# Sheet1.net
KiCad netlist of a schematic drawn in Altium Designer
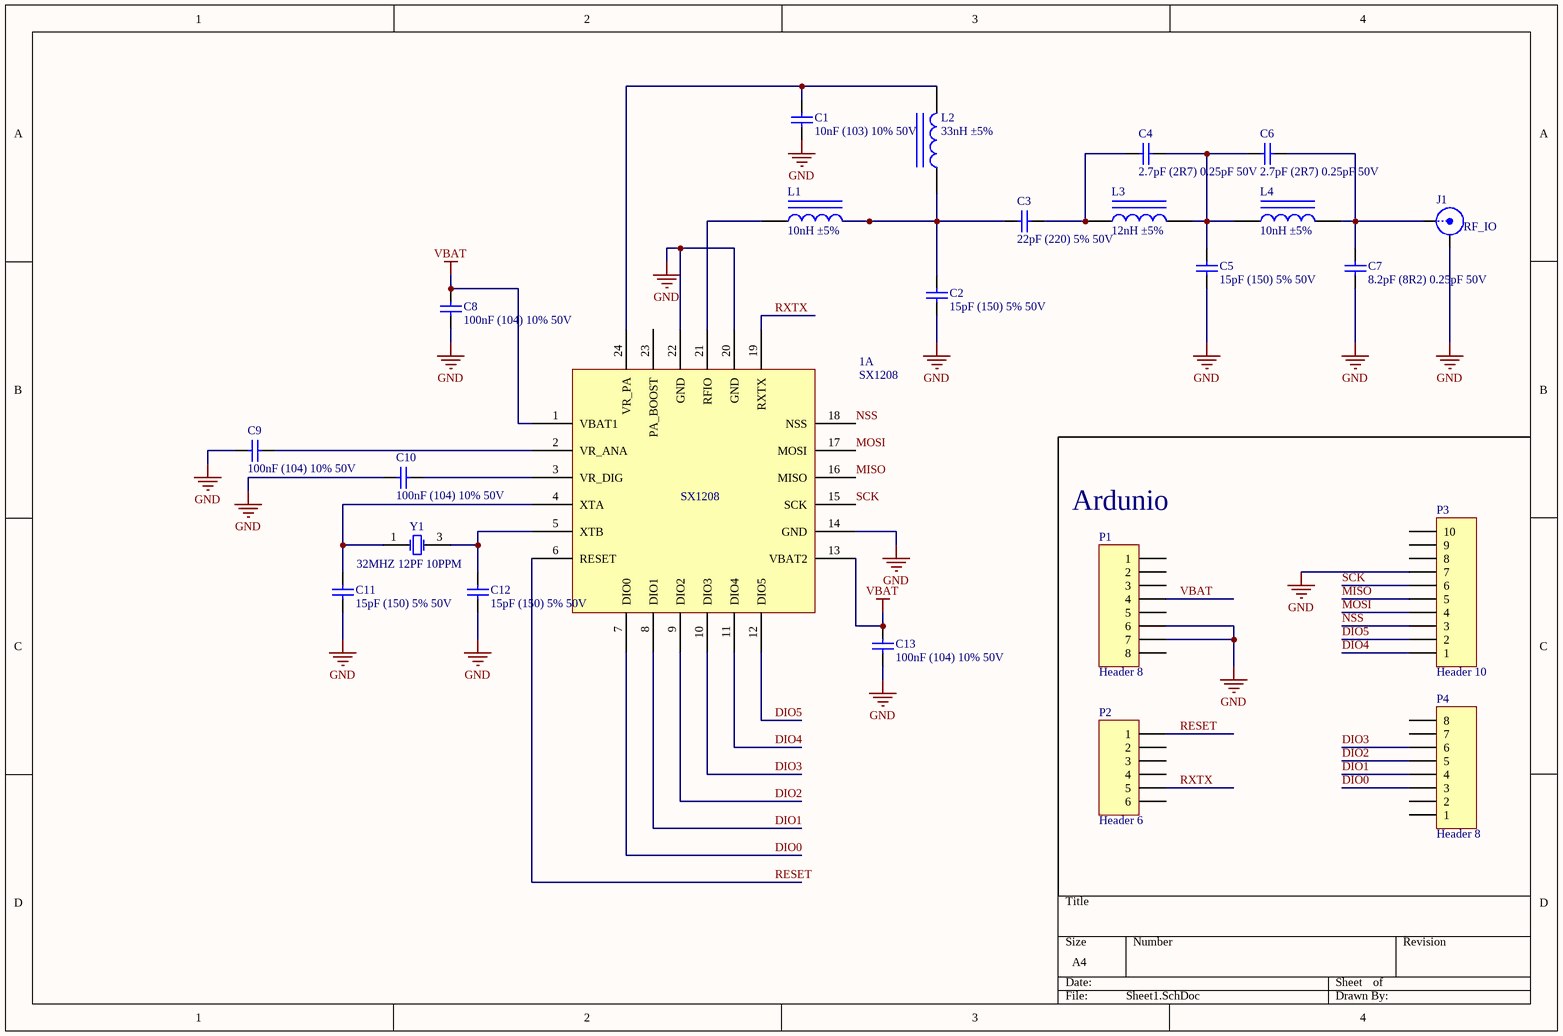
[diagram p0: Sheet1.SchDoc]

(export (version "E")
  (design (tool "Eeschema 10.0.6"))
  (components
    (comp (ref "1")
      (value "SX1208")
      (footprint "QFN-24_4x4x05P")
      (libsource (lib "SX1208") (part "Component_1"))
    )
    (comp (ref "C1")
      (value "10nF (103) 10% 50V")
      (footprint "0603_C")
      (description "贴片电容")
      (libsource (lib "Miscellaneous Devices LC") (part "0603 10nF (103) 10% 50V"))
    )
    (comp (ref "C2")
      (value "15pF (150) 5% 50V")
      (footprint "0603_C")
      (description "贴片电容")
      (libsource (lib "Miscellaneous Devices LC") (part "0603 15pF (150) 5% 50V"))
    )
    (comp (ref "C3")
      (value "22pF (220) 5% 50V")
      (footprint "0603_C")
      (description "贴片电容")
      (libsource (lib "Miscellaneous Devices LC") (part "0603 22pF (220) 5% 50V"))
    )
    (comp (ref "C4")
      (value "2.7pF (2R7) 0.25pF 50V")
      (footprint "0603_C")
      (description "贴片电容")
      (libsource (lib "Miscellaneous Devices LC") (part "0603 2.7pF (2R7) 0.25pF 50V"))
    )
    (comp (ref "C5")
      (value "15pF (150) 5% 50V")
      (footprint "0603_C")
      (description "贴片电容")
      (libsource (lib "Miscellaneous Devices LC") (part "0603 15pF (150) 5% 50V"))
    )
    (comp (ref "C6")
      (value "2.7pF (2R7) 0.25pF 50V")
      (footprint "0603_C")
      (description "贴片电容")
      (libsource (lib "Miscellaneous Devices LC") (part "0603 2.7pF (2R7) 0.25pF 50V"))
    )
    (comp (ref "C7")
      (value "8.2pF (8R2) 0.25pF 50V")
      (footprint "0603_C")
      (description "贴片电容")
      (libsource (lib "Miscellaneous Devices LC") (part "0603 8.2pF (8R2) 0.25pF 50V"))
    )
    (comp (ref "C8")
      (value "100nF (104) 10% 50V")
      (footprint "0603_C")
      (description "贴片电容")
      (libsource (lib "Miscellaneous Devices LC") (part "0603 100nF (104) 10% 50V"))
    )
    (comp (ref "C9")
      (value "100nF (104) 10% 50V")
      (footprint "0603_C")
      (description "贴片电容")
      (libsource (lib "Miscellaneous Devices LC") (part "0603 100nF (104) 10% 50V"))
    )
    (comp (ref "C10")
      (value "100nF (104) 10% 50V")
      (footprint "0603_C")
      (description "贴片电容")
      (libsource (lib "Miscellaneous Devices LC") (part "0603 100nF (104) 10% 50V"))
    )
    (comp (ref "C11")
      (value "15pF (150) 5% 50V")
      (footprint "0603_C")
      (description "贴片电容")
      (libsource (lib "Miscellaneous Devices LC") (part "0603 15pF (150) 5% 50V"))
    )
    (comp (ref "C12")
      (value "15pF (150) 5% 50V")
      (footprint "0603_C")
      (description "贴片电容")
      (libsource (lib "Miscellaneous Devices LC") (part "0603 15pF (150) 5% 50V"))
    )
    (comp (ref "C13")
      (value "100nF (104) 10% 50V")
      (footprint "0603_C")
      (description "贴片电容")
      (libsource (lib "Miscellaneous Devices LC") (part "0603 100nF (104) 10% 50V"))
    )
    (comp (ref "J1")
      (value "RF_IO")
      (footprint "PCBComponent_1")
      (description "SMB Straight Connector")
      (fields (field (name "PUBLISHER") "Altium Limited"))
      (libsource (lib "Miscellaneous Connectors") (part "SMB"))
    )
    (comp (ref "L1")
      (value "10nH ±5%")
      (footprint "0603_L")
      (description "贴片电感")
      (libsource (lib "Miscellaneous Devices LC") (part "0603 10nH 5%"))
    )
    (comp (ref "L2")
      (value "33nH ±5%")
      (footprint "0603_L")
      (description "贴片电感")
      (libsource (lib "Miscellaneous Devices LC") (part "0603 33nH 5%"))
    )
    (comp (ref "L3")
      (value "12nH ±5%")
      (footprint "0603_L")
      (description "贴片电感")
      (libsource (lib "Miscellaneous Devices LC") (part "0603 12nH 5%"))
    )
    (comp (ref "L4")
      (value "10nH ±5%")
      (footprint "0603_L")
      (description "贴片电感")
      (libsource (lib "Miscellaneous Devices LC") (part "0603 10nH 5%"))
    )
    (comp (ref "P1")
      (value "Header 8")
      (footprint "HDR1X8")
      (description "Header, 8-Pin")
      (fields (field (name "PUBLISHER") "Altium Limited"))
      (libsource (lib "Miscellaneous Connectors") (part "Header 8"))
    )
    (comp (ref "P2")
      (value "Header 6")
      (footprint "HDR1X6")
      (description "Header, 6-Pin")
      (fields (field (name "PUBLISHER") "Altium Limited"))
      (libsource (lib "Miscellaneous Connectors") (part "Header 6"))
    )
    (comp (ref "P3")
      (value "Header 10")
      (footprint "HDR1X10")
      (description "Header, 10-Pin")
      (fields (field (name "PUBLISHER") "Altium Limited"))
      (libsource (lib "Miscellaneous Connectors") (part "Header 10"))
    )
    (comp (ref "P4")
      (value "Header 8")
      (footprint "HDR1X8")
      (description "Header, 8-Pin")
      (fields (field (name "PUBLISHER") "Altium Limited"))
      (libsource (lib "") (part "Header 8_1"))
    )
    (comp (ref "Y1")
      (value "32MHZ 12PF 10PPM")
      (footprint "SMD-3225_4P")
      (description "贴片晶振")
      (libsource (lib "Miscellaneous Devices LC") (part "SMD-3225_4P  25MHZ 12PF 10PPM"))
    )
  )
  (nets
    (net (code "2") (name "/DIO0") (class "Default")
      (node (ref "1") (pin "7") (pinfunction "DIO0_7") (pintype "passive"))
      (node (ref "P4") (pin "3") (pinfunction "3_3") (pintype "passive"))
    )
    (net (code "3") (name "/DIO1") (class "Default")
      (node (ref "1") (pin "8") (pinfunction "DIO1_8") (pintype "passive"))
      (node (ref "P4") (pin "4") (pinfunction "4_4") (pintype "passive"))
    )
    (net (code "4") (name "/DIO2") (class "Default")
      (node (ref "1") (pin "9") (pinfunction "DIO2_9") (pintype "passive"))
      (node (ref "P4") (pin "5") (pinfunction "5_5") (pintype "passive"))
    )
    (net (code "5") (name "/DIO3") (class "Default")
      (node (ref "1") (pin "10") (pinfunction "DIO3_10") (pintype "passive"))
      (node (ref "P4") (pin "6") (pinfunction "6_6") (pintype "passive"))
    )
    (net (code "6") (name "/DIO4") (class "Default")
      (node (ref "1") (pin "11") (pinfunction "DIO4_11") (pintype "passive"))
      (node (ref "P3") (pin "1") (pinfunction "1_1") (pintype "passive"))
    )
    (net (code "7") (name "/DIO5") (class "Default")
      (node (ref "1") (pin "12") (pinfunction "DIO5_12") (pintype "passive"))
      (node (ref "P3") (pin "2") (pinfunction "2_2") (pintype "passive"))
    )
    (net (code "8") (name "/MISO") (class "Default")
      (node (ref "1") (pin "16") (pinfunction "MISO_16") (pintype "passive"))
      (node (ref "P3") (pin "5") (pinfunction "5_5") (pintype "passive"))
    )
    (net (code "9") (name "/MOSI") (class "Default")
      (node (ref "1") (pin "17") (pinfunction "MOSI_17") (pintype "passive"))
      (node (ref "P3") (pin "4") (pinfunction "4_4") (pintype "passive"))
    )
    (net (code "10") (name "/NSS") (class "Default")
      (node (ref "1") (pin "18") (pinfunction "NSS_18") (pintype "passive"))
      (node (ref "P3") (pin "3") (pinfunction "3_3") (pintype "passive"))
    )
    (net (code "11") (name "/RESET") (class "Default")
      (node (ref "1") (pin "6") (pinfunction "RESET_6") (pintype "passive"))
      (node (ref "P2") (pin "1") (pinfunction "1_1") (pintype "passive"))
    )
    (net (code "12") (name "/RXTX") (class "Default")
      (node (ref "1") (pin "19") (pinfunction "RXTX_19") (pintype "passive"))
      (node (ref "P2") (pin "5") (pinfunction "5_5") (pintype "passive"))
    )
    (net (code "13") (name "/SCK") (class "Default")
      (node (ref "1") (pin "15") (pinfunction "SCK_15") (pintype "passive"))
      (node (ref "P3") (pin "6") (pinfunction "6_6") (pintype "passive"))
    )
    (net (code "14") (name "GND") (class "Default")
      (node (ref "1") (pin "14") (pinfunction "GND_14") (pintype "passive"))
      (node (ref "1") (pin "20") (pinfunction "GND_20") (pintype "passive"))
      (node (ref "1") (pin "22") (pinfunction "GND_22") (pintype "passive"))
      (node (ref "C1") (pin "1") (pinfunction "1_1") (pintype "passive"))
      (node (ref "C10") (pin "2") (pinfunction "2_2") (pintype "passive"))
      (node (ref "C11") (pin "1") (pinfunction "1_1") (pintype "passive"))
      (node (ref "C12") (pin "1") (pinfunction "1_1") (pintype "passive"))
      (node (ref "C13") (pin "1") (pinfunction "1_1") (pintype "passive"))
      (node (ref "C2") (pin "1") (pinfunction "1_1") (pintype "passive"))
      (node (ref "C5") (pin "1") (pinfunction "1_1") (pintype "passive"))
      (node (ref "C7") (pin "1") (pinfunction "1_1") (pintype "passive"))
      (node (ref "C8") (pin "1") (pinfunction "1_1") (pintype "passive"))
      (node (ref "C9") (pin "2") (pinfunction "2_2") (pintype "passive"))
      (node (ref "J1") (pin "2") (pinfunction "Y_2") (pintype "passive"))
      (node (ref "P1") (pin "6") (pinfunction "6_6") (pintype "passive"))
      (node (ref "P1") (pin "7") (pinfunction "7_7") (pintype "passive"))
      (node (ref "P3") (pin "7") (pinfunction "7_7") (pintype "passive"))
    )
    (net (code "15") (name "Net-(1-RFIO)") (class "Default")
      (node (ref "1") (pin "21") (pinfunction "RFIO_21") (pintype "passive"))
      (node (ref "L1") (pin "1") (pinfunction "1_1") (pintype "passive"))
    )
    (net (code "16") (name "Net-(1-VR_ANA)") (class "Default")
      (node (ref "1") (pin "2") (pinfunction "VR_ANA_2") (pintype "passive"))
      (node (ref "C9") (pin "1") (pinfunction "1_1") (pintype "passive"))
    )
    (net (code "17") (name "Net-(1-VR_DIG)") (class "Default")
      (node (ref "1") (pin "3") (pinfunction "VR_DIG_3") (pintype "passive"))
      (node (ref "C10") (pin "1") (pinfunction "1_1") (pintype "passive"))
    )
    (net (code "18") (name "Net-(1-VR_PA)") (class "Default")
      (node (ref "1") (pin "24") (pinfunction "VR_PA_24") (pintype "passive"))
      (node (ref "C1") (pin "2") (pinfunction "2_2") (pintype "passive"))
      (node (ref "L2") (pin "2") (pinfunction "2_2") (pintype "passive"))
    )
    (net (code "19") (name "Net-(1-XTA)") (class "Default")
      (node (ref "1") (pin "4") (pinfunction "XTA_4") (pintype "passive"))
      (node (ref "C11") (pin "2") (pinfunction "2_2") (pintype "passive"))
      (node (ref "Y1") (pin "1") (pinfunction "OSC1_1") (pintype "passive"))
    )
    (net (code "20") (name "Net-(1-XTB)") (class "Default")
      (node (ref "1") (pin "5") (pinfunction "XTB_5") (pintype "passive"))
      (node (ref "C12") (pin "2") (pinfunction "2_2") (pintype "passive"))
      (node (ref "Y1") (pin "3") (pinfunction "OSC2_3") (pintype "passive"))
    )
    (net (code "21") (name "Net-(C2-Pad2)") (class "Default")
      (node (ref "C2") (pin "2") (pinfunction "2_2") (pintype "passive"))
      (node (ref "C3") (pin "1") (pinfunction "1_1") (pintype "passive"))
      (node (ref "L1") (pin "2") (pinfunction "2_2") (pintype "passive"))
      (node (ref "L2") (pin "1") (pinfunction "1_1") (pintype "passive"))
    )
    (net (code "22") (name "Net-(C3-Pad2)") (class "Default")
      (node (ref "C3") (pin "2") (pinfunction "2_2") (pintype "passive"))
      (node (ref "C4") (pin "1") (pinfunction "1_1") (pintype "passive"))
      (node (ref "L3") (pin "1") (pinfunction "1_1") (pintype "passive"))
    )
    (net (code "23") (name "Net-(C4-Pad2)") (class "Default")
      (node (ref "C4") (pin "2") (pinfunction "2_2") (pintype "passive"))
      (node (ref "C5") (pin "2") (pinfunction "2_2") (pintype "passive"))
      (node (ref "C6") (pin "1") (pinfunction "1_1") (pintype "passive"))
      (node (ref "L3") (pin "2") (pinfunction "2_2") (pintype "passive"))
      (node (ref "L4") (pin "1") (pinfunction "1_1") (pintype "passive"))
    )
    (net (code "24") (name "Net-(J1-X)") (class "Default")
      (node (ref "C6") (pin "2") (pinfunction "2_2") (pintype "passive"))
      (node (ref "C7") (pin "2") (pinfunction "2_2") (pintype "passive"))
      (node (ref "J1") (pin "1") (pinfunction "X_1") (pintype "passive"))
      (node (ref "L4") (pin "2") (pinfunction "2_2") (pintype "passive"))
    )
    (net (code "25") (name "VBAT") (class "Default")
      (node (ref "1") (pin "1") (pinfunction "VBAT1_1") (pintype "passive"))
      (node (ref "1") (pin "13") (pinfunction "VBAT2_13") (pintype "passive"))
      (node (ref "C13") (pin "2") (pinfunction "2_2") (pintype "passive"))
      (node (ref "C8") (pin "2") (pinfunction "2_2") (pintype "passive"))
      (node (ref "P1") (pin "4") (pinfunction "4_4") (pintype "passive"))
    )
    (net (code "26") (name "unconnected-(1-PA_BOOST-Pad23)") (class "Default")
      (node (ref "1") (pin "23") (pinfunction "PA_BOOST_23") (pintype "passive"))
    )
    (net (code "27") (name "unconnected-(P1-Pad1)") (class "Default")
      (node (ref "P1") (pin "1") (pinfunction "1_1") (pintype "passive"))
    )
    (net (code "28") (name "unconnected-(P1-Pad2)") (class "Default")
      (node (ref "P1") (pin "2") (pinfunction "2_2") (pintype "passive"))
    )
    (net (code "29") (name "unconnected-(P1-Pad3)") (class "Default")
      (node (ref "P1") (pin "3") (pinfunction "3_3") (pintype "passive"))
    )
    (net (code "30") (name "unconnected-(P1-Pad5)") (class "Default")
      (node (ref "P1") (pin "5") (pinfunction "5_5") (pintype "passive"))
    )
    (net (code "31") (name "unconnected-(P1-Pad8)") (class "Default")
      (node (ref "P1") (pin "8") (pinfunction "8_8") (pintype "passive"))
    )
    (net (code "32") (name "unconnected-(P2-Pad2)") (class "Default")
      (node (ref "P2") (pin "2") (pinfunction "2_2") (pintype "passive"))
    )
    (net (code "33") (name "unconnected-(P2-Pad3)") (class "Default")
      (node (ref "P2") (pin "3") (pinfunction "3_3") (pintype "passive"))
    )
    (net (code "34") (name "unconnected-(P2-Pad4)") (class "Default")
      (node (ref "P2") (pin "4") (pinfunction "4_4") (pintype "passive"))
    )
    (net (code "35") (name "unconnected-(P2-Pad6)") (class "Default")
      (node (ref "P2") (pin "6") (pinfunction "6_6") (pintype "passive"))
    )
    (net (code "36") (name "unconnected-(P3-Pad8)") (class "Default")
      (node (ref "P3") (pin "8") (pinfunction "8_8") (pintype "passive"))
    )
    (net (code "37") (name "unconnected-(P3-Pad9)") (class "Default")
      (node (ref "P3") (pin "9") (pinfunction "9_9") (pintype "passive"))
    )
    (net (code "38") (name "unconnected-(P3-Pad10)") (class "Default")
      (node (ref "P3") (pin "10") (pinfunction "10_10") (pintype "passive"))
    )
    (net (code "39") (name "unconnected-(P4-Pad1)") (class "Default")
      (node (ref "P4") (pin "1") (pinfunction "1_1") (pintype "passive"))
    )
    (net (code "40") (name "unconnected-(P4-Pad2)") (class "Default")
      (node (ref "P4") (pin "2") (pinfunction "2_2") (pintype "passive"))
    )
    (net (code "41") (name "unconnected-(P4-Pad7)") (class "Default")
      (node (ref "P4") (pin "7") (pinfunction "7_7") (pintype "passive"))
    )
    (net (code "42") (name "unconnected-(P4-Pad8)") (class "Default")
      (node (ref "P4") (pin "8") (pinfunction "8_8") (pintype "passive"))
    )
  )
)
